# 11_Zynq_MIO.net
KiCad netlist of a schematic drawn in Altium Designer
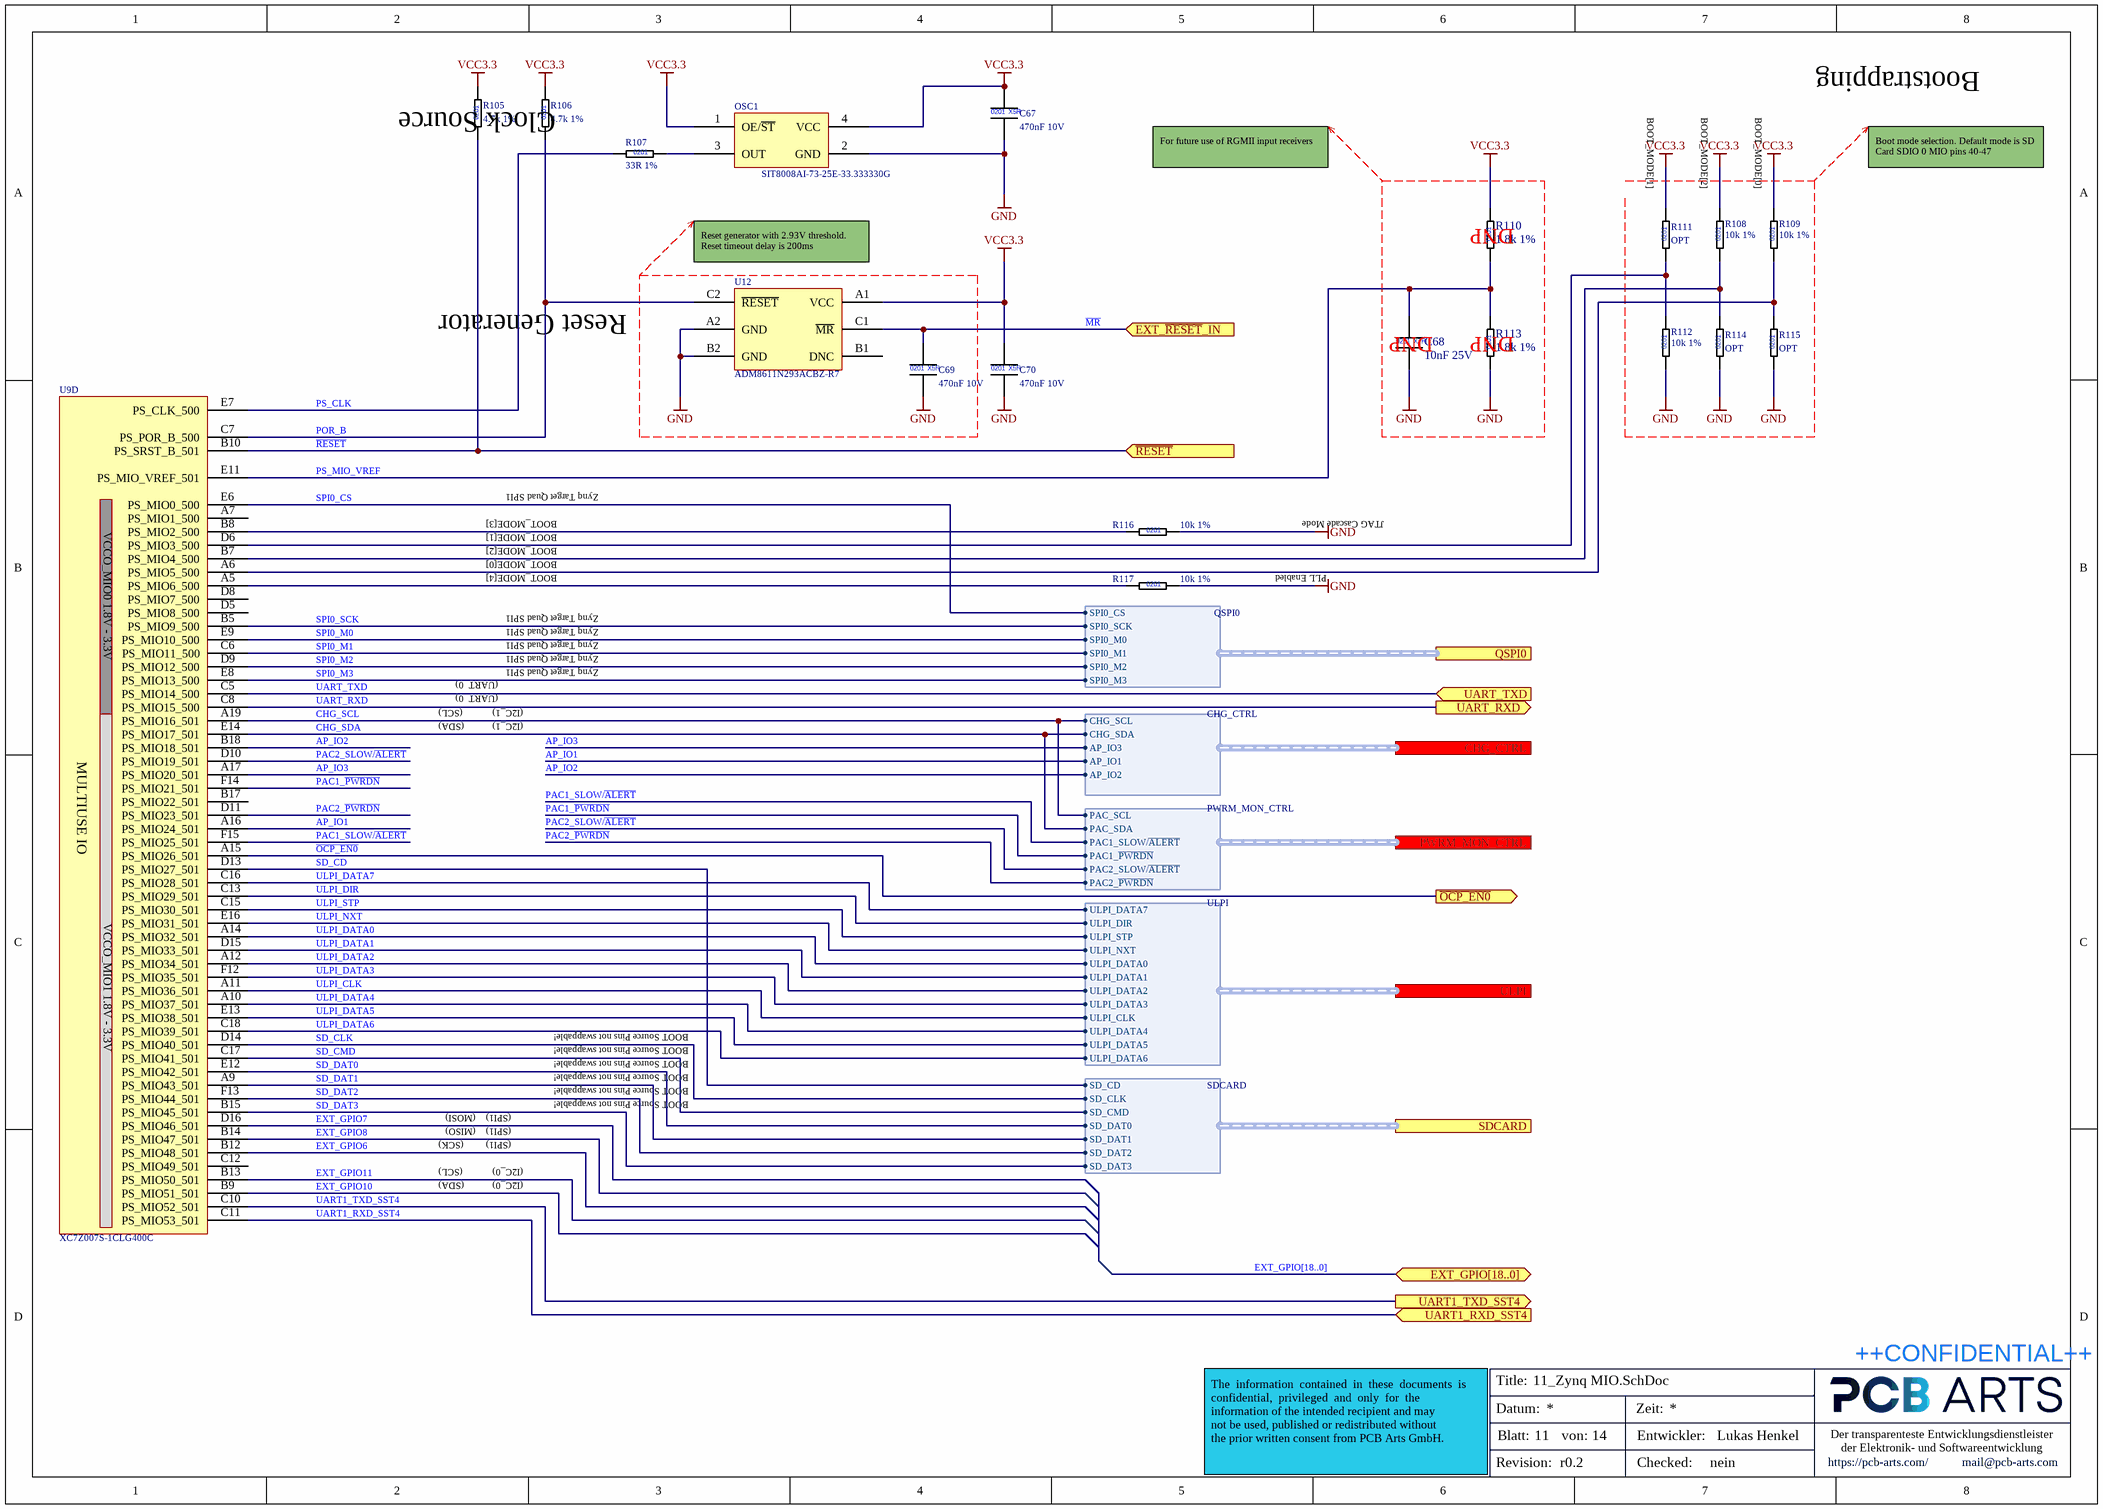
[diagram p0: 11_Zynq MIO.SchDoc]

(export (version "E")
  (design (tool "Eeschema 10.0.6"))
  (components
    (comp (ref "C67")
      (value "470nF 10V")
      (footprint "Zynq-Feather-HD:CAPC0603X03L")
      (description "Multilayer Ceramic Capacitors MLCC - SMD/SMT 0201 10VDC")
      (libsource (lib "Zynq-Feather-HD") (part "CAP_0201_470nF_10V"))
    )
    (comp (ref "C68")
      (value "10nF 25V")
      (footprint "Zynq-Feather-HD:CAPC0603X03L")
      (description "Multilayer Ceramic Capacitors MLCC - SMD/SMT 0201 25VDC")
      (libsource (lib "Zynq-Feather-HD") (part "CAP_0201_10nF_25V"))
    )
    (comp (ref "C69")
      (value "470nF 10V")
      (footprint "Zynq-Feather-HD:CAPC0603X03L")
      (description "Multilayer Ceramic Capacitors MLCC - SMD/SMT 0201 10VDC")
      (libsource (lib "Zynq-Feather-HD") (part "CAP_0201_470nF_10V"))
    )
    (comp (ref "C70")
      (value "470nF 10V")
      (footprint "Zynq-Feather-HD:CAPC0603X03L")
      (description "Multilayer Ceramic Capacitors MLCC - SMD/SMT 0201 10VDC")
      (libsource (lib "Zynq-Feather-HD") (part "CAP_0201_470nF_10V"))
    )
    (comp (ref "OSC1")
      (value "SIT8008AI-73-25E-33.333330G")
      (footprint "Zynq-Feather-HD:SiT8008")
      (description "Standard Clock Oscillators 33.33333MHz 2.5V 50ppm -40C +85C")
      (libsource (lib "Zynq-Feather-HD") (part "SIT8008AI_Clock Oscillators 33.33333MHz"))
    )
    (comp (ref "R105")
      (value "4.7k 1%")
      (footprint "Zynq-Feather-HD:RESC0603X03L")
      (description "Thick Film Resistors - SMD 4.7K OHM 1%")
      (libsource (lib "Zynq-Feather-HD") (part "RES_0201_4.7k_1%"))
    )
    (comp (ref "R106")
      (value "4.7k 1%")
      (footprint "Zynq-Feather-HD:RESC0603X03L")
      (description "Thick Film Resistors - SMD 4.7K OHM 1%")
      (libsource (lib "Zynq-Feather-HD") (part "RES_0201_4.7k_1%"))
    )
    (comp (ref "R107")
      (value "33R 1%")
      (footprint "Zynq-Feather-HD:RESC0603X03L")
      (description "Thick Film Resistors - SMD 33R OHM 1%")
      (libsource (lib "Zynq-Feather-HD") (part "RES_0201_33R_1%"))
    )
    (comp (ref "R108")
      (value "10k 1%")
      (footprint "Zynq-Feather-HD:RESC0603X03L")
      (description "Thick Film Resistors - SMD 10K OHM 1%")
      (libsource (lib "Zynq-Feather-HD") (part "RES_0201_10k_1%"))
    )
    (comp (ref "R109")
      (value "10k 1%")
      (footprint "Zynq-Feather-HD:RESC0603X03L")
      (description "Thick Film Resistors - SMD 10K OHM 1%")
      (libsource (lib "Zynq-Feather-HD") (part "RES_0201_10k_1%"))
    )
    (comp (ref "R110")
      (value "1.8k 1%")
      (footprint "Zynq-Feather-HD:RESC0603X03L")
      (description "Thick Film Resistors - SMD 1.8K OHM 1%")
      (libsource (lib "Zynq-Feather-HD") (part "RES_0201_1.8k_1%"))
    )
    (comp (ref "R111")
      (value "OPT")
      (footprint "Zynq-Feather-HD:RESC0603X03L")
      (description "Thick Film Resistors - SMD Optinal")
      (libsource (lib "Zynq-Feather-HD") (part "RES_0201_OPT"))
    )
    (comp (ref "R112")
      (value "10k 1%")
      (footprint "Zynq-Feather-HD:RESC0603X03L")
      (description "Thick Film Resistors - SMD 10K OHM 1%")
      (libsource (lib "Zynq-Feather-HD") (part "RES_0201_10k_1%"))
    )
    (comp (ref "R113")
      (value "1.8k 1%")
      (footprint "Zynq-Feather-HD:RESC0603X03L")
      (description "Thick Film Resistors - SMD 1.8K OHM 1%")
      (libsource (lib "Zynq-Feather-HD") (part "RES_0201_1.8k_1%"))
    )
    (comp (ref "R114")
      (value "OPT")
      (footprint "Zynq-Feather-HD:RESC0603X03L")
      (description "Thick Film Resistors - SMD Optinal")
      (libsource (lib "Zynq-Feather-HD") (part "RES_0201_OPT"))
    )
    (comp (ref "R115")
      (value "OPT")
      (footprint "Zynq-Feather-HD:RESC0603X03L")
      (description "Thick Film Resistors - SMD Optinal")
      (libsource (lib "Zynq-Feather-HD") (part "RES_0201_OPT"))
    )
    (comp (ref "R116")
      (value "10k 1%")
      (footprint "Zynq-Feather-HD:RESC0603X03L")
      (description "Thick Film Resistors - SMD 10K OHM 1%")
      (libsource (lib "Zynq-Feather-HD") (part "RES_0201_10k_1%"))
    )
    (comp (ref "R117")
      (value "10k 1%")
      (footprint "Zynq-Feather-HD:RESC0603X03L")
      (description "Thick Film Resistors - SMD 10K OHM 1%")
      (libsource (lib "Zynq-Feather-HD") (part "RES_0201_10k_1%"))
    )
    (comp (ref "U9")
      (value "XC7Z007S-1CLG400C")
      (footprint "Zynq-Feather-HD:BGA400C80P20X20_1700X1700X160")
      (description "XC7Z007S-1CLG400C_Processors - Application Specialised")
      (libsource (lib "Zynq-Feather-HD") (part "XC7Z007S-1CLG400C_Processors - Application Specialised"))
    )
    (comp (ref "U12")
      (value "ADM8611N293ACBZ-R7")
      (footprint "zynq-feather-hd:BGA6C50P2X3_96X146X66")
      (description "Supervisory Circuits IC, Reset Only ULP Supervisory Circuit")
      (libsource (lib "Zynq-Feather-HD") (part "ADM8611N293ACBZ-R7_Supervisory Circuits IC"))
    )
  )
  (nets
    (net (code "20") (name "/AP_IO1") (class "Default")
      (node (ref "U9") (pin "A16") (pinfunction "PS_MIO24_501_A16") (pintype "passive"))
    )
    (net (code "21") (name "/AP_IO2") (class "Default")
      (node (ref "U9") (pin "B18") (pinfunction "PS_MIO18_501_B18") (pintype "passive"))
    )
    (net (code "22") (name "/AP_IO3") (class "Default")
      (node (ref "U9") (pin "A17") (pinfunction "PS_MIO20_501_A17") (pintype "passive"))
    )
    (net (code "23") (name "/CHG_SCL") (class "Default")
      (node (ref "U9") (pin "A19") (pinfunction "PS_MIO16_501_A19") (pintype "passive"))
    )
    (net (code "24") (name "/CHG_SDA") (class "Default")
      (node (ref "U9") (pin "E14") (pinfunction "PS_MIO17_501_E14") (pintype "passive"))
    )
    (net (code "25") (name "/EXT_GPIO6") (class "Default")
      (node (ref "U9") (pin "B12") (pinfunction "PS_MIO48_501_B12") (pintype "passive"))
    )
    (net (code "26") (name "/EXT_GPIO7") (class "Default")
      (node (ref "U9") (pin "D16") (pinfunction "PS_MIO46_501_D16") (pintype "passive"))
    )
    (net (code "27") (name "/EXT_GPIO8") (class "Default")
      (node (ref "U9") (pin "B14") (pinfunction "PS_MIO47_501_B14") (pintype "passive"))
    )
    (net (code "28") (name "/EXT_GPIO10") (class "Default")
      (node (ref "U9") (pin "B9") (pinfunction "PS_MIO51_501_B9") (pintype "passive"))
    )
    (net (code "29") (name "/EXT_GPIO11") (class "Default")
      (node (ref "U9") (pin "B13") (pinfunction "PS_MIO50_501_B13") (pintype "passive"))
    )
    (net (code "31") (name "/PAC1_SLOW{slash}~{ALERT}") (class "Default")
      (node (ref "U9") (pin "F15") (pinfunction "PS_MIO25_501_F15") (pintype "passive"))
    )
    (net (code "32") (name "/PAC1_~{PWRDN}") (class "Default")
      (node (ref "U9") (pin "F14") (pinfunction "PS_MIO21_501_F14") (pintype "passive"))
    )
    (net (code "33") (name "/PAC2_SLOW{slash}~{ALERT}") (class "Default")
      (node (ref "U9") (pin "D10") (pinfunction "PS_MIO19_501_D10") (pintype "passive"))
    )
    (net (code "34") (name "/PAC2_~{PWRDN}") (class "Default")
      (node (ref "U9") (pin "D11") (pinfunction "PS_MIO23_501_D11") (pintype "passive"))
    )
    (net (code "35") (name "/POR_B") (class "Default")
      (node (ref "R106") (pin "1") (pinfunction "1_1") (pintype "passive"))
      (node (ref "U12") (pin "C2") (pinfunction "~{RESET}_C2") (pintype "passive"))
      (node (ref "U9") (pin "C7") (pinfunction "PS_POR_B_500_C7") (pintype "passive"))
    )
    (net (code "36") (name "/PS_CLK") (class "Default")
      (node (ref "R107") (pin "1") (pinfunction "1_1") (pintype "passive"))
      (node (ref "U9") (pin "E7") (pinfunction "PS_CLK_500_E7") (pintype "passive"))
    )
    (net (code "37") (name "/PS_MIO_VREF") (class "Default")
      (node (ref "C68") (pin "1") (pinfunction "1_1") (pintype "passive"))
      (node (ref "R110") (pin "1") (pinfunction "1_1") (pintype "passive"))
      (node (ref "R113") (pin "2") (pinfunction "2_2") (pintype "passive"))
      (node (ref "U9") (pin "E11") (pinfunction "PS_MIO_VREF_501_E11") (pintype "passive"))
    )
    (net (code "38") (name "/SD_CD") (class "Default")
      (node (ref "U9") (pin "D13") (pinfunction "PS_MIO27_501_D13") (pintype "passive"))
    )
    (net (code "39") (name "/SD_CLK") (class "Default")
      (node (ref "U9") (pin "D14") (pinfunction "PS_MIO40_501_D14") (pintype "passive"))
    )
    (net (code "40") (name "/SD_CMD") (class "Default")
      (node (ref "U9") (pin "C17") (pinfunction "PS_MIO41_501_C17") (pintype "passive"))
    )
    (net (code "41") (name "/SD_DAT0") (class "Default")
      (node (ref "U9") (pin "E12") (pinfunction "PS_MIO42_501_E12") (pintype "passive"))
    )
    (net (code "42") (name "/SD_DAT1") (class "Default")
      (node (ref "U9") (pin "A9") (pinfunction "PS_MIO43_501_A9") (pintype "passive"))
    )
    (net (code "43") (name "/SD_DAT2") (class "Default")
      (node (ref "U9") (pin "F13") (pinfunction "PS_MIO44_501_F13") (pintype "passive"))
    )
    (net (code "44") (name "/SD_DAT3") (class "Default")
      (node (ref "U9") (pin "B15") (pinfunction "PS_MIO45_501_B15") (pintype "passive"))
    )
    (net (code "45") (name "/SPI0_CS") (class "Default")
      (node (ref "U9") (pin "E6") (pinfunction "PS_MIO0_500_E6") (pintype "passive"))
    )
    (net (code "46") (name "/SPI0_M0") (class "Default")
      (node (ref "U9") (pin "E9") (pinfunction "PS_MIO10_500_E9") (pintype "passive"))
    )
    (net (code "47") (name "/SPI0_M1") (class "Default")
      (node (ref "U9") (pin "C6") (pinfunction "PS_MIO11_500_C6") (pintype "passive"))
    )
    (net (code "48") (name "/SPI0_M2") (class "Default")
      (node (ref "U9") (pin "D9") (pinfunction "PS_MIO12_500_D9") (pintype "passive"))
    )
    (net (code "49") (name "/SPI0_M3") (class "Default")
      (node (ref "U9") (pin "E8") (pinfunction "PS_MIO13_500_E8") (pintype "passive"))
    )
    (net (code "50") (name "/SPI0_SCK") (class "Default")
      (node (ref "U9") (pin "B5") (pinfunction "PS_MIO9_500_B5") (pintype "passive"))
    )
    (net (code "51") (name "/UART1_RXD_SST4") (class "Default")
      (node (ref "U9") (pin "C11") (pinfunction "PS_MIO53_501_C11") (pintype "passive"))
    )
    (net (code "52") (name "/UART1_TXD_SST4") (class "Default")
      (node (ref "U9") (pin "C10") (pinfunction "PS_MIO52_501_C10") (pintype "passive"))
    )
    (net (code "53") (name "/UART_RXD") (class "Default")
      (node (ref "U9") (pin "C8") (pinfunction "PS_MIO15_500_C8") (pintype "passive"))
    )
    (net (code "54") (name "/UART_TXD") (class "Default")
      (node (ref "U9") (pin "C5") (pinfunction "PS_MIO14_500_C5") (pintype "passive"))
    )
    (net (code "55") (name "/ULPI_CLK") (class "Default")
      (node (ref "U9") (pin "A11") (pinfunction "PS_MIO36_501_A11") (pintype "passive"))
    )
    (net (code "56") (name "/ULPI_DATA0") (class "Default")
      (node (ref "U9") (pin "A14") (pinfunction "PS_MIO32_501_A14") (pintype "passive"))
    )
    (net (code "57") (name "/ULPI_DATA1") (class "Default")
      (node (ref "U9") (pin "D15") (pinfunction "PS_MIO33_501_D15") (pintype "passive"))
    )
    (net (code "58") (name "/ULPI_DATA2") (class "Default")
      (node (ref "U9") (pin "A12") (pinfunction "PS_MIO34_501_A12") (pintype "passive"))
    )
    (net (code "59") (name "/ULPI_DATA3") (class "Default")
      (node (ref "U9") (pin "F12") (pinfunction "PS_MIO35_501_F12") (pintype "passive"))
    )
    (net (code "60") (name "/ULPI_DATA4") (class "Default")
      (node (ref "U9") (pin "A10") (pinfunction "PS_MIO37_501_A10") (pintype "passive"))
    )
    (net (code "61") (name "/ULPI_DATA5") (class "Default")
      (node (ref "U9") (pin "E13") (pinfunction "PS_MIO38_501_E13") (pintype "passive"))
    )
    (net (code "62") (name "/ULPI_DATA6") (class "Default")
      (node (ref "U9") (pin "C18") (pinfunction "PS_MIO39_501_C18") (pintype "passive"))
    )
    (net (code "63") (name "/ULPI_DATA7") (class "Default")
      (node (ref "U9") (pin "C16") (pinfunction "PS_MIO28_501_C16") (pintype "passive"))
    )
    (net (code "64") (name "/ULPI_DIR") (class "Default")
      (node (ref "U9") (pin "C13") (pinfunction "PS_MIO29_501_C13") (pintype "passive"))
    )
    (net (code "65") (name "/ULPI_NXT") (class "Default")
      (node (ref "U9") (pin "E16") (pinfunction "PS_MIO31_501_E16") (pintype "passive"))
    )
    (net (code "66") (name "/ULPI_STP") (class "Default")
      (node (ref "U9") (pin "C15") (pinfunction "PS_MIO30_501_C15") (pintype "passive"))
    )
    (net (code "72") (name "/~{MR}") (class "Default")
      (node (ref "C69") (pin "1") (pinfunction "1_1") (pintype "passive"))
      (node (ref "U12") (pin "C1") (pinfunction "~{MR}_C1") (pintype "passive"))
    )
    (net (code "73") (name "/~{OCP_EN0}") (class "Default")
      (node (ref "U9") (pin "A15") (pinfunction "PS_MIO26_501_A15") (pintype "passive"))
    )
    (net (code "74") (name "/~{RESET}") (class "Default")
      (node (ref "R105") (pin "1") (pinfunction "1_1") (pintype "passive"))
      (node (ref "U9") (pin "B10") (pinfunction "PS_SRST_B_501_B10") (pintype "passive"))
    )
    (net (code "75") (name "GND") (class "Default")
      (node (ref "C67") (pin "2") (pinfunction "2_2") (pintype "passive"))
      (node (ref "C68") (pin "2") (pinfunction "2_2") (pintype "passive"))
      (node (ref "C69") (pin "2") (pinfunction "2_2") (pintype "passive"))
      (node (ref "C70") (pin "2") (pinfunction "2_2") (pintype "passive"))
      (node (ref "OSC1") (pin "2") (pinfunction "GND_2") (pintype "passive"))
      (node (ref "R112") (pin "1") (pinfunction "1_1") (pintype "passive"))
      (node (ref "R113") (pin "1") (pinfunction "1_1") (pintype "passive"))
      (node (ref "R114") (pin "1") (pinfunction "1_1") (pintype "passive"))
      (node (ref "R115") (pin "1") (pinfunction "1_1") (pintype "passive"))
      (node (ref "R116") (pin "2") (pinfunction "2_2") (pintype "passive"))
      (node (ref "R117") (pin "2") (pinfunction "2_2") (pintype "passive"))
      (node (ref "U12") (pin "A2") (pinfunction "GND_A2") (pintype "passive"))
      (node (ref "U12") (pin "B2") (pinfunction "GND_B2") (pintype "passive"))
    )
    (net (code "76") (name "Net-(OSC1-OUT)") (class "Default")
      (node (ref "OSC1") (pin "3") (pinfunction "OUT_3") (pintype "passive"))
      (node (ref "R107") (pin "2") (pinfunction "2_2") (pintype "passive"))
    )
    (net (code "77") (name "Net-(U9D-PS_MIO2_500)") (class "Default")
      (node (ref "R116") (pin "1") (pinfunction "1_1") (pintype "passive"))
      (node (ref "U9") (pin "B8") (pinfunction "PS_MIO2_500_B8") (pintype "passive"))
    )
    (net (code "78") (name "Net-(U9D-PS_MIO3_500)") (class "Default")
      (node (ref "R111") (pin "1") (pinfunction "1_1") (pintype "passive"))
      (node (ref "R112") (pin "2") (pinfunction "2_2") (pintype "passive"))
      (node (ref "U9") (pin "D6") (pinfunction "PS_MIO3_500_D6") (pintype "passive"))
    )
    (net (code "79") (name "Net-(U9D-PS_MIO4_500)") (class "Default")
      (node (ref "R108") (pin "1") (pinfunction "1_1") (pintype "passive"))
      (node (ref "R114") (pin "2") (pinfunction "2_2") (pintype "passive"))
      (node (ref "U9") (pin "B7") (pinfunction "PS_MIO4_500_B7") (pintype "passive"))
    )
    (net (code "80") (name "Net-(U9D-PS_MIO5_500)") (class "Default")
      (node (ref "R109") (pin "1") (pinfunction "1_1") (pintype "passive"))
      (node (ref "R115") (pin "2") (pinfunction "2_2") (pintype "passive"))
      (node (ref "U9") (pin "A6") (pinfunction "PS_MIO5_500_A6") (pintype "passive"))
    )
    (net (code "81") (name "Net-(U9D-PS_MIO6_500)") (class "Default")
      (node (ref "R117") (pin "1") (pinfunction "1_1") (pintype "passive"))
      (node (ref "U9") (pin "A5") (pinfunction "PS_MIO6_500_A5") (pintype "passive"))
    )
    (net (code "82") (name "VCC3.3") (class "Default")
      (node (ref "C67") (pin "1") (pinfunction "1_1") (pintype "passive"))
      (node (ref "C70") (pin "1") (pinfunction "1_1") (pintype "passive"))
      (node (ref "OSC1") (pin "1") (pinfunction "OE/~{ST}_1") (pintype "passive"))
      (node (ref "OSC1") (pin "4") (pinfunction "VCC_4") (pintype "passive"))
      (node (ref "R105") (pin "2") (pinfunction "2_2") (pintype "passive"))
      (node (ref "R106") (pin "2") (pinfunction "2_2") (pintype "passive"))
      (node (ref "R108") (pin "2") (pinfunction "2_2") (pintype "passive"))
      (node (ref "R109") (pin "2") (pinfunction "2_2") (pintype "passive"))
      (node (ref "R110") (pin "2") (pinfunction "2_2") (pintype "passive"))
      (node (ref "R111") (pin "2") (pinfunction "2_2") (pintype "passive"))
      (node (ref "U12") (pin "A1") (pinfunction "VCC_A1") (pintype "passive"))
    )
    (net (code "83") (name "unconnected-(U9D-PS_MIO1_500-PadA7)") (class "Default")
      (node (ref "U9") (pin "A7") (pinfunction "PS_MIO1_500_A7") (pintype "passive"))
    )
    (net (code "84") (name "unconnected-(U9D-PS_MIO7_500-PadD8)") (class "Default")
      (node (ref "U9") (pin "D8") (pinfunction "PS_MIO7_500_D8") (pintype "passive"))
    )
    (net (code "85") (name "unconnected-(U9D-PS_MIO8_500-PadD5)") (class "Default")
      (node (ref "U9") (pin "D5") (pinfunction "PS_MIO8_500_D5") (pintype "passive"))
    )
    (net (code "86") (name "unconnected-(U9D-PS_MIO22_501-PadB17)") (class "Default")
      (node (ref "U9") (pin "B17") (pinfunction "PS_MIO22_501_B17") (pintype "passive"))
    )
    (net (code "87") (name "unconnected-(U9D-PS_MIO49_501-PadC12)") (class "Default")
      (node (ref "U9") (pin "C12") (pinfunction "PS_MIO49_501_C12") (pintype "passive"))
    )
    (net (code "88") (name "unconnected-(U12-DNC-PadB1)") (class "Default")
      (node (ref "U12") (pin "B1") (pinfunction "DNC_B1") (pintype "passive"))
    )
  )
)
